# simple_flip_flop.net
KiCad netlist of a schematic drawn in EAGLE
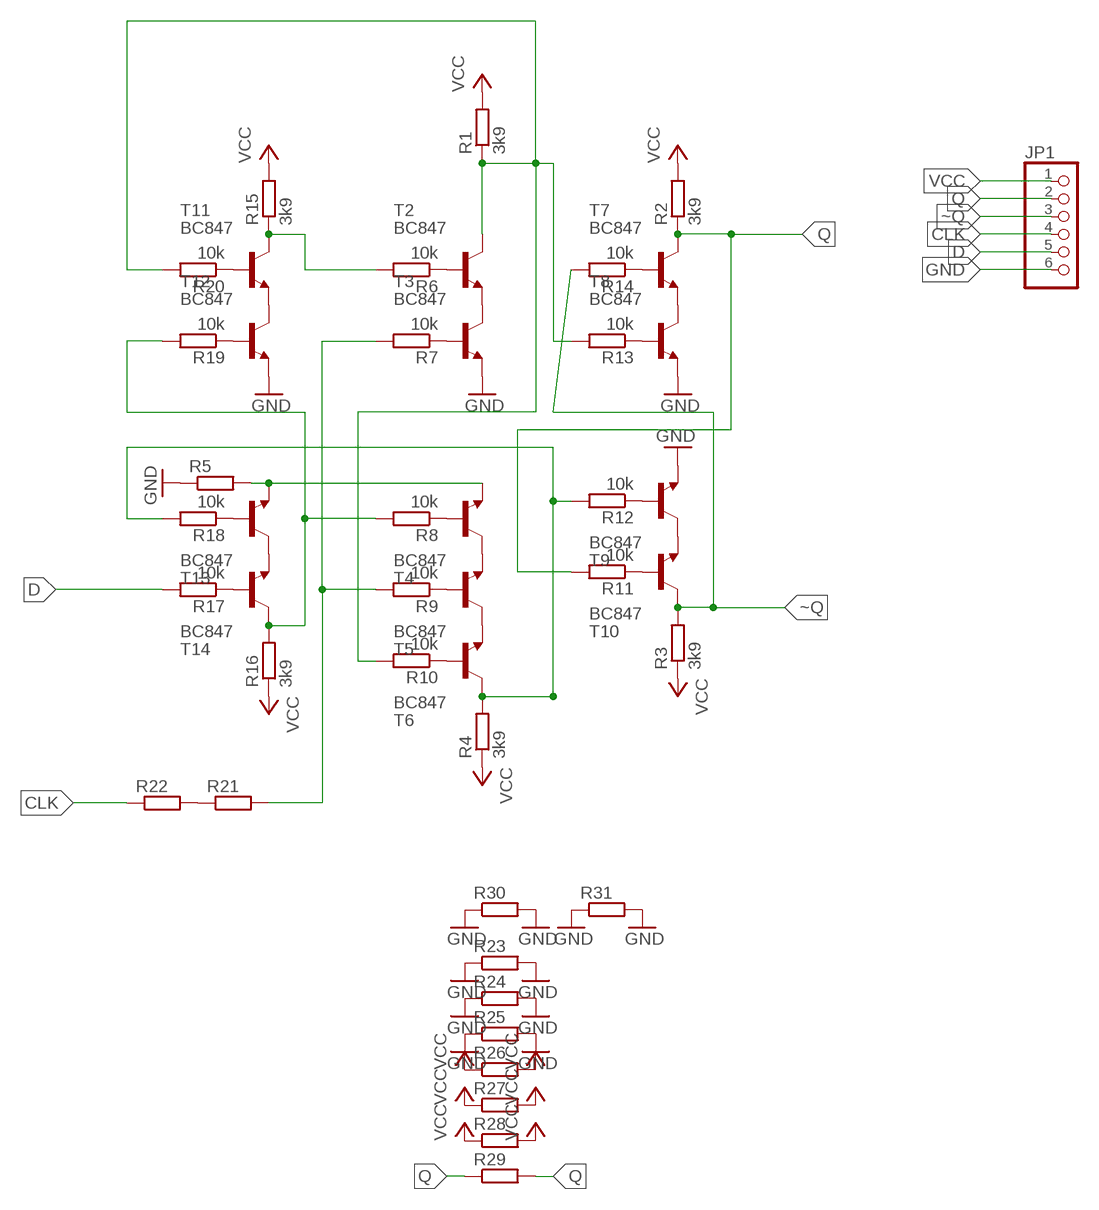
[diagram p0: schematic, sheet 1]

(export (version "E")
  (design (tool "Eeschema 10.0.6"))
  (components
    (comp (ref "JP1")
      (value "PINHD-1X06_2.54-SMD")
      (footprint "eagle-import:1X06SMD")
      (libsource (lib "eagle-import") (part "PINHD-1X06_2.54-SMD"))
    )
    (comp (ref "R1")
      (value "3k9")
      (footprint "eagle-import:R0805W")
      (libsource (lib "eagle-import") (part "R-EU_R0805W"))
    )
    (comp (ref "R2")
      (value "3k9")
      (footprint "eagle-import:R0805W")
      (libsource (lib "eagle-import") (part "R-EU_R0805W"))
    )
    (comp (ref "R3")
      (value "3k9")
      (footprint "eagle-import:R0805W")
      (libsource (lib "eagle-import") (part "R-EU_R0805W"))
    )
    (comp (ref "R4")
      (value "3k9")
      (footprint "eagle-import:R0805W")
      (libsource (lib "eagle-import") (part "R-EU_R0805W"))
    )
    (comp (ref "R5")
      (value "R-EU_R1206")
      (footprint "eagle-import:R1206")
      (libsource (lib "eagle-import") (part "resistor_348_R-EU_R1206"))
    )
    (comp (ref "R6")
      (value "10k")
      (footprint "eagle-import:R0805W")
      (libsource (lib "eagle-import") (part "R-EU_R0805W"))
    )
    (comp (ref "R7")
      (value "10k")
      (footprint "eagle-import:R0805W")
      (libsource (lib "eagle-import") (part "R-EU_R0805W"))
    )
    (comp (ref "R8")
      (value "10k")
      (footprint "eagle-import:R0805W")
      (libsource (lib "eagle-import") (part "R-EU_R0805W"))
    )
    (comp (ref "R9")
      (value "10k")
      (footprint "eagle-import:R0805W")
      (libsource (lib "eagle-import") (part "R-EU_R0805W"))
    )
    (comp (ref "R10")
      (value "10k")
      (footprint "eagle-import:R0805W")
      (libsource (lib "eagle-import") (part "R-EU_R0805W"))
    )
    (comp (ref "R11")
      (value "10k")
      (footprint "eagle-import:R0805W")
      (libsource (lib "eagle-import") (part "R-EU_R0805W"))
    )
    (comp (ref "R12")
      (value "10k")
      (footprint "eagle-import:R0805W")
      (libsource (lib "eagle-import") (part "R-EU_R0805W"))
    )
    (comp (ref "R13")
      (value "10k")
      (footprint "eagle-import:R0805W")
      (libsource (lib "eagle-import") (part "R-EU_R0805W"))
    )
    (comp (ref "R14")
      (value "10k")
      (footprint "eagle-import:R0805W")
      (libsource (lib "eagle-import") (part "R-EU_R0805W"))
    )
    (comp (ref "R15")
      (value "3k9")
      (footprint "eagle-import:R0805W")
      (libsource (lib "eagle-import") (part "R-EU_R0805W"))
    )
    (comp (ref "R16")
      (value "3k9")
      (footprint "eagle-import:R0805W")
      (libsource (lib "eagle-import") (part "R-EU_R0805W"))
    )
    (comp (ref "R17")
      (value "10k")
      (footprint "eagle-import:R0805W")
      (libsource (lib "eagle-import") (part "R-EU_R0805W"))
    )
    (comp (ref "R18")
      (value "10k")
      (footprint "eagle-import:R0805W")
      (libsource (lib "eagle-import") (part "R-EU_R0805W"))
    )
    (comp (ref "R19")
      (value "10k")
      (footprint "eagle-import:R0805W")
      (libsource (lib "eagle-import") (part "R-EU_R0805W"))
    )
    (comp (ref "R20")
      (value "10k")
      (footprint "eagle-import:R0805W")
      (libsource (lib "eagle-import") (part "R-EU_R0805W"))
    )
    (comp (ref "R21")
      (value "R-EU_R1206")
      (footprint "eagle-import:R1206")
      (libsource (lib "eagle-import") (part "resistor_348_R-EU_R1206"))
    )
    (comp (ref "R22")
      (value "R-EU_R1206")
      (footprint "eagle-import:R1206")
      (libsource (lib "eagle-import") (part "resistor_348_R-EU_R1206"))
    )
    (comp (ref "R23")
      (value "R-EU_R1206")
      (footprint "eagle-import:R1206")
      (libsource (lib "eagle-import") (part "resistor_348_R-EU_R1206"))
    )
    (comp (ref "R24")
      (value "R-EU_R1206")
      (footprint "eagle-import:R1206")
      (libsource (lib "eagle-import") (part "resistor_348_R-EU_R1206"))
    )
    (comp (ref "R25")
      (value "R-EU_R1206")
      (footprint "eagle-import:R1206")
      (libsource (lib "eagle-import") (part "resistor_348_R-EU_R1206"))
    )
    (comp (ref "R26")
      (value "R-EU_R1206")
      (footprint "eagle-import:R1206")
      (libsource (lib "eagle-import") (part "resistor_348_R-EU_R1206"))
    )
    (comp (ref "R27")
      (value "R-EU_R1206")
      (footprint "eagle-import:R1206")
      (libsource (lib "eagle-import") (part "resistor_348_R-EU_R1206"))
    )
    (comp (ref "R28")
      (value "R-EU_R1206")
      (footprint "eagle-import:R1206")
      (libsource (lib "eagle-import") (part "resistor_348_R-EU_R1206"))
    )
    (comp (ref "R29")
      (value "R-EU_R1206")
      (footprint "eagle-import:R1206")
      (libsource (lib "eagle-import") (part "R-EU_R1206"))
    )
    (comp (ref "R30")
      (value "R-EU_R1206")
      (footprint "eagle-import:R1206")
      (libsource (lib "eagle-import") (part "resistor_348_R-EU_R1206"))
    )
    (comp (ref "R31")
      (value "R-EU_R1206")
      (footprint "eagle-import:R1206")
      (libsource (lib "eagle-import") (part "resistor_348_R-EU_R1206"))
    )
    (comp (ref "T2")
      (value "BC847")
      (footprint "eagle-import:SOT23")
      (libsource (lib "eagle-import") (part "BC847"))
    )
    (comp (ref "T3")
      (value "BC847")
      (footprint "eagle-import:SOT23")
      (libsource (lib "eagle-import") (part "BC847"))
    )
    (comp (ref "T4")
      (value "BC847")
      (footprint "eagle-import:SOT23")
      (libsource (lib "eagle-import") (part "BC847"))
    )
    (comp (ref "T5")
      (value "BC847")
      (footprint "eagle-import:SOT23")
      (libsource (lib "eagle-import") (part "BC847"))
    )
    (comp (ref "T6")
      (value "BC847")
      (footprint "eagle-import:SOT23")
      (libsource (lib "eagle-import") (part "BC847"))
    )
    (comp (ref "T7")
      (value "BC847")
      (footprint "eagle-import:SOT23")
      (libsource (lib "eagle-import") (part "BC847"))
    )
    (comp (ref "T8")
      (value "BC847")
      (footprint "eagle-import:SOT23")
      (libsource (lib "eagle-import") (part "BC847"))
    )
    (comp (ref "T9")
      (value "BC847")
      (footprint "eagle-import:SOT23")
      (libsource (lib "eagle-import") (part "BC847"))
    )
    (comp (ref "T10")
      (value "BC847")
      (footprint "eagle-import:SOT23")
      (libsource (lib "eagle-import") (part "BC847"))
    )
    (comp (ref "T11")
      (value "BC847")
      (footprint "eagle-import:SOT23")
      (libsource (lib "eagle-import") (part "BC847"))
    )
    (comp (ref "T12")
      (value "BC847")
      (footprint "eagle-import:SOT23")
      (libsource (lib "eagle-import") (part "BC847"))
    )
    (comp (ref "T13")
      (value "BC847")
      (footprint "eagle-import:SOT23")
      (libsource (lib "eagle-import") (part "BC847"))
    )
    (comp (ref "T14")
      (value "BC847")
      (footprint "eagle-import:SOT23")
      (libsource (lib "eagle-import") (part "BC847"))
    )
  )
  (nets
    (net (code "1") (name "/~{Q}") (class "Default")
      (node (ref "JP1") (pin "3") (pinfunction "3_3") (pintype "passive"))
      (node (ref "R14") (pin "2") (pinfunction "2_2") (pintype "passive"))
      (node (ref "R3") (pin "2") (pinfunction "2_2") (pintype "passive"))
      (node (ref "T10") (pin "3") (pinfunction "C_3") (pintype "passive"))
    )
    (net (code "2") (name "CLK") (class "Default")
      (node (ref "JP1") (pin "4") (pinfunction "4_4") (pintype "passive"))
      (node (ref "R22") (pin "1") (pinfunction "1_1") (pintype "passive"))
    )
    (net (code "3") (name "D") (class "Default")
      (node (ref "JP1") (pin "5") (pinfunction "5_5") (pintype "passive"))
      (node (ref "R17") (pin "2") (pinfunction "2_2") (pintype "passive"))
    )
    (net (code "4") (name "GND") (class "Default")
      (node (ref "JP1") (pin "6") (pinfunction "6_6") (pintype "passive"))
      (node (ref "R23") (pin "1") (pinfunction "1_1") (pintype "passive"))
      (node (ref "R23") (pin "2") (pinfunction "2_2") (pintype "passive"))
      (node (ref "R24") (pin "1") (pinfunction "1_1") (pintype "passive"))
      (node (ref "R24") (pin "2") (pinfunction "2_2") (pintype "passive"))
      (node (ref "R25") (pin "1") (pinfunction "1_1") (pintype "passive"))
      (node (ref "R25") (pin "2") (pinfunction "2_2") (pintype "passive"))
      (node (ref "R30") (pin "1") (pinfunction "1_1") (pintype "passive"))
      (node (ref "R30") (pin "2") (pinfunction "2_2") (pintype "passive"))
      (node (ref "R31") (pin "1") (pinfunction "1_1") (pintype "passive"))
      (node (ref "R31") (pin "2") (pinfunction "2_2") (pintype "passive"))
      (node (ref "R5") (pin "1") (pinfunction "1_1") (pintype "passive"))
      (node (ref "T12") (pin "2") (pinfunction "E_2") (pintype "passive"))
      (node (ref "T3") (pin "2") (pinfunction "E_2") (pintype "passive"))
      (node (ref "T8") (pin "2") (pinfunction "E_2") (pintype "passive"))
      (node (ref "T9") (pin "2") (pinfunction "E_2") (pintype "passive"))
    )
    (net (code "5") (name "Net-(R21-Pad1)") (class "Default")
      (node (ref "R21") (pin "1") (pinfunction "1_1") (pintype "passive"))
      (node (ref "R22") (pin "2") (pinfunction "2_2") (pintype "passive"))
    )
    (net (code "6") (name "Net-(R21-Pad2)") (class "Default")
      (node (ref "R21") (pin "2") (pinfunction "2_2") (pintype "passive"))
      (node (ref "R7") (pin "2") (pinfunction "2_2") (pintype "passive"))
      (node (ref "R9") (pin "2") (pinfunction "2_2") (pintype "passive"))
    )
    (net (code "7") (name "Net-(T2-B)") (class "Default")
      (node (ref "R6") (pin "1") (pinfunction "1_1") (pintype "passive"))
      (node (ref "T2") (pin "1") (pinfunction "B_1") (pintype "passive"))
    )
    (net (code "8") (name "Net-(T2-C)") (class "Default")
      (node (ref "R1") (pin "1") (pinfunction "1_1") (pintype "passive"))
      (node (ref "R10") (pin "2") (pinfunction "2_2") (pintype "passive"))
      (node (ref "R13") (pin "2") (pinfunction "2_2") (pintype "passive"))
      (node (ref "R20") (pin "2") (pinfunction "2_2") (pintype "passive"))
      (node (ref "T2") (pin "3") (pinfunction "C_3") (pintype "passive"))
    )
    (net (code "9") (name "Net-(T2-E)") (class "Default")
      (node (ref "T2") (pin "2") (pinfunction "E_2") (pintype "passive"))
      (node (ref "T3") (pin "3") (pinfunction "C_3") (pintype "passive"))
    )
    (net (code "10") (name "Net-(T3-B)") (class "Default")
      (node (ref "R7") (pin "1") (pinfunction "1_1") (pintype "passive"))
      (node (ref "T3") (pin "1") (pinfunction "B_1") (pintype "passive"))
    )
    (net (code "11") (name "Net-(T4-B)") (class "Default")
      (node (ref "R8") (pin "1") (pinfunction "1_1") (pintype "passive"))
      (node (ref "T4") (pin "1") (pinfunction "B_1") (pintype "passive"))
    )
    (net (code "12") (name "Net-(T4-C)") (class "Default")
      (node (ref "T4") (pin "3") (pinfunction "C_3") (pintype "passive"))
      (node (ref "T5") (pin "2") (pinfunction "E_2") (pintype "passive"))
    )
    (net (code "13") (name "Net-(T5-B)") (class "Default")
      (node (ref "R9") (pin "1") (pinfunction "1_1") (pintype "passive"))
      (node (ref "T5") (pin "1") (pinfunction "B_1") (pintype "passive"))
    )
    (net (code "14") (name "Net-(T5-C)") (class "Default")
      (node (ref "T5") (pin "3") (pinfunction "C_3") (pintype "passive"))
      (node (ref "T6") (pin "2") (pinfunction "E_2") (pintype "passive"))
    )
    (net (code "15") (name "Net-(T6-B)") (class "Default")
      (node (ref "R10") (pin "1") (pinfunction "1_1") (pintype "passive"))
      (node (ref "T6") (pin "1") (pinfunction "B_1") (pintype "passive"))
    )
    (net (code "16") (name "Net-(T6-C)") (class "Default")
      (node (ref "R12") (pin "2") (pinfunction "2_2") (pintype "passive"))
      (node (ref "R18") (pin "2") (pinfunction "2_2") (pintype "passive"))
      (node (ref "R4") (pin "2") (pinfunction "2_2") (pintype "passive"))
      (node (ref "T6") (pin "3") (pinfunction "C_3") (pintype "passive"))
    )
    (net (code "17") (name "Net-(T7-B)") (class "Default")
      (node (ref "R14") (pin "1") (pinfunction "1_1") (pintype "passive"))
      (node (ref "T7") (pin "1") (pinfunction "B_1") (pintype "passive"))
    )
    (net (code "18") (name "Net-(T7-E)") (class "Default")
      (node (ref "T7") (pin "2") (pinfunction "E_2") (pintype "passive"))
      (node (ref "T8") (pin "3") (pinfunction "C_3") (pintype "passive"))
    )
    (net (code "19") (name "Net-(T8-B)") (class "Default")
      (node (ref "R13") (pin "1") (pinfunction "1_1") (pintype "passive"))
      (node (ref "T8") (pin "1") (pinfunction "B_1") (pintype "passive"))
    )
    (net (code "20") (name "Net-(T9-B)") (class "Default")
      (node (ref "R12") (pin "1") (pinfunction "1_1") (pintype "passive"))
      (node (ref "T9") (pin "1") (pinfunction "B_1") (pintype "passive"))
    )
    (net (code "21") (name "Net-(T10-B)") (class "Default")
      (node (ref "R11") (pin "1") (pinfunction "1_1") (pintype "passive"))
      (node (ref "T10") (pin "1") (pinfunction "B_1") (pintype "passive"))
    )
    (net (code "22") (name "Net-(T10-E)") (class "Default")
      (node (ref "T10") (pin "2") (pinfunction "E_2") (pintype "passive"))
      (node (ref "T9") (pin "3") (pinfunction "C_3") (pintype "passive"))
    )
    (net (code "23") (name "Net-(T11-B)") (class "Default")
      (node (ref "R20") (pin "1") (pinfunction "1_1") (pintype "passive"))
      (node (ref "T11") (pin "1") (pinfunction "B_1") (pintype "passive"))
    )
    (net (code "24") (name "Net-(T11-C)") (class "Default")
      (node (ref "R15") (pin "1") (pinfunction "1_1") (pintype "passive"))
      (node (ref "R6") (pin "2") (pinfunction "2_2") (pintype "passive"))
      (node (ref "T11") (pin "3") (pinfunction "C_3") (pintype "passive"))
    )
    (net (code "25") (name "Net-(T11-E)") (class "Default")
      (node (ref "T11") (pin "2") (pinfunction "E_2") (pintype "passive"))
      (node (ref "T12") (pin "3") (pinfunction "C_3") (pintype "passive"))
    )
    (net (code "26") (name "Net-(T12-B)") (class "Default")
      (node (ref "R19") (pin "1") (pinfunction "1_1") (pintype "passive"))
      (node (ref "T12") (pin "1") (pinfunction "B_1") (pintype "passive"))
    )
    (net (code "27") (name "Net-(T13-B)") (class "Default")
      (node (ref "R18") (pin "1") (pinfunction "1_1") (pintype "passive"))
      (node (ref "T13") (pin "1") (pinfunction "B_1") (pintype "passive"))
    )
    (net (code "28") (name "Net-(T13-C)") (class "Default")
      (node (ref "T13") (pin "3") (pinfunction "C_3") (pintype "passive"))
      (node (ref "T14") (pin "2") (pinfunction "E_2") (pintype "passive"))
    )
    (net (code "29") (name "Net-(T13-E)") (class "Default")
      (node (ref "R5") (pin "2") (pinfunction "2_2") (pintype "passive"))
      (node (ref "T13") (pin "2") (pinfunction "E_2") (pintype "passive"))
      (node (ref "T4") (pin "2") (pinfunction "E_2") (pintype "passive"))
    )
    (net (code "30") (name "Net-(T14-B)") (class "Default")
      (node (ref "R17") (pin "1") (pinfunction "1_1") (pintype "passive"))
      (node (ref "T14") (pin "1") (pinfunction "B_1") (pintype "passive"))
    )
    (net (code "31") (name "Net-(T14-C)") (class "Default")
      (node (ref "R16") (pin "2") (pinfunction "2_2") (pintype "passive"))
      (node (ref "R19") (pin "2") (pinfunction "2_2") (pintype "passive"))
      (node (ref "R8") (pin "2") (pinfunction "2_2") (pintype "passive"))
      (node (ref "T14") (pin "3") (pinfunction "C_3") (pintype "passive"))
    )
    (net (code "32") (name "Q") (class "Default")
      (node (ref "JP1") (pin "2") (pinfunction "2_2") (pintype "passive"))
      (node (ref "R11") (pin "2") (pinfunction "2_2") (pintype "passive"))
      (node (ref "R2") (pin "1") (pinfunction "1_1") (pintype "passive"))
      (node (ref "R29") (pin "1") (pinfunction "1_1") (pintype "passive"))
      (node (ref "R29") (pin "2") (pinfunction "2_2") (pintype "passive"))
      (node (ref "T7") (pin "3") (pinfunction "C_3") (pintype "passive"))
    )
    (net (code "33") (name "VCC") (class "Default")
      (node (ref "JP1") (pin "1") (pinfunction "1_1") (pintype "passive"))
      (node (ref "R1") (pin "2") (pinfunction "2_2") (pintype "passive"))
      (node (ref "R15") (pin "2") (pinfunction "2_2") (pintype "passive"))
      (node (ref "R16") (pin "1") (pinfunction "1_1") (pintype "passive"))
      (node (ref "R2") (pin "2") (pinfunction "2_2") (pintype "passive"))
      (node (ref "R26") (pin "1") (pinfunction "1_1") (pintype "passive"))
      (node (ref "R26") (pin "2") (pinfunction "2_2") (pintype "passive"))
      (node (ref "R27") (pin "1") (pinfunction "1_1") (pintype "passive"))
      (node (ref "R27") (pin "2") (pinfunction "2_2") (pintype "passive"))
      (node (ref "R28") (pin "1") (pinfunction "1_1") (pintype "passive"))
      (node (ref "R28") (pin "2") (pinfunction "2_2") (pintype "passive"))
      (node (ref "R3") (pin "1") (pinfunction "1_1") (pintype "passive"))
      (node (ref "R4") (pin "1") (pinfunction "1_1") (pintype "passive"))
    )
  )
)
